# IDD_measurement.net
KiCad netlist of a schematic drawn in Altium Designer
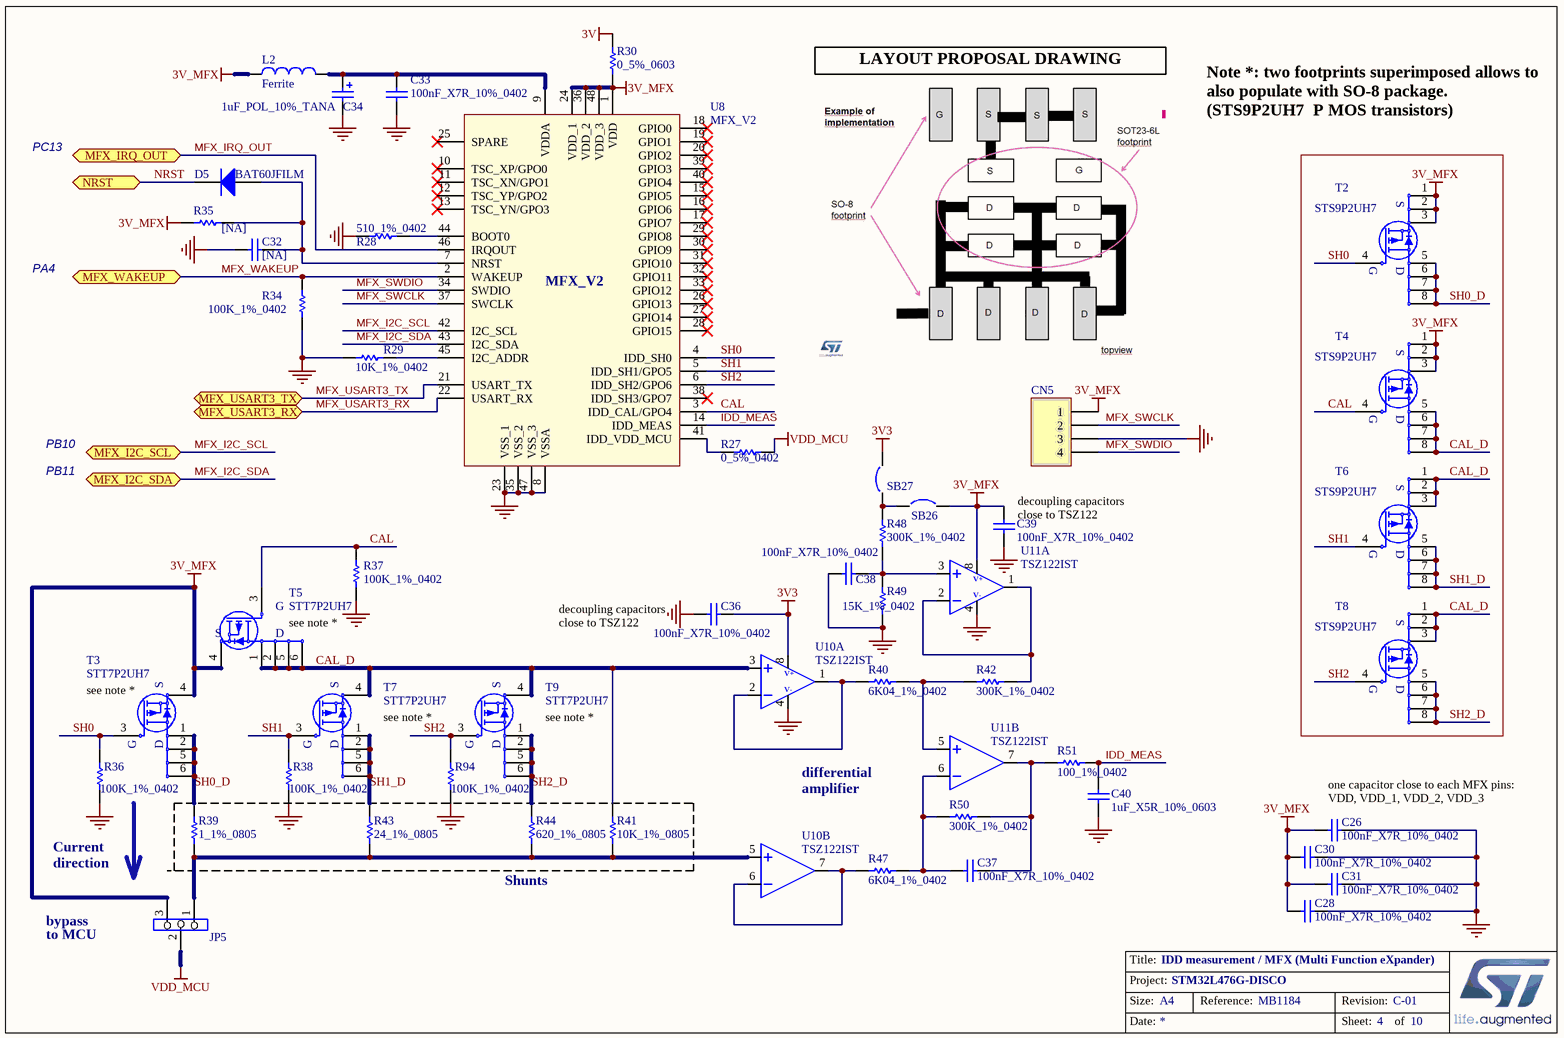
[diagram p0: IDD_measurement.SchDoc]

(export (version "E")
  (design (tool "Eeschema 10.0.6"))
  (components
    (comp (ref "C26")
      (value "100nF_X7R_10%_0402")
      (footprint "0402C")
      (description "Capacitor,100nF,16V,X7R,10%,0402,YAGEO")
      (libsource (lib "MCD_TOOLS") (part "Cap_100nF_X7R_10%_0402"))
    )
    (comp (ref "C28")
      (value "100nF_X7R_10%_0402")
      (footprint "0402C")
      (description "Capacitor,100nF,16V,X7R,10%,0402,YAGEO")
      (libsource (lib "MCD_TOOLS") (part "Cap_100nF_X7R_10%_0402"))
    )
    (comp (ref "C30")
      (value "100nF_X7R_10%_0402")
      (footprint "0402C")
      (description "Capacitor,100nF,16V,X7R,10%,0402,YAGEO")
      (libsource (lib "MCD_TOOLS") (part "Cap_100nF_X7R_10%_0402"))
    )
    (comp (ref "C31")
      (value "100nF_X7R_10%_0402")
      (footprint "0402C")
      (description "Capacitor,100nF,16V,X7R,10%,0402,YAGEO")
      (libsource (lib "MCD_TOOLS") (part "Cap_100nF_X7R_10%_0402"))
    )
    (comp (ref "C32")
      (value "[NA]")
      (footprint "0402C")
      (description "Capacitor,NA,0402")
      (libsource (lib "MCD_TOOLS") (part "Cap_NA_0402"))
    )
    (comp (ref "C33")
      (value "100nF_X7R_10%_0402")
      (footprint "0402C")
      (description "Capacitor,100nF,16V,X7R,10%,0402,YAGEO")
      (libsource (lib "MCD_TOOLS") (part "Cap_100nF_X7R_10%_0402"))
    )
    (comp (ref "C34")
      (value "1uF_POL_10%_TANA")
      (footprint "TAN-A")
      (description "Polarized Capacitor,1uF,16V,10%,typeA,AVX")
      (libsource (lib "MCD_TOOLS") (part "Cap_1uF_POL_10%_TANA"))
    )
    (comp (ref "C36")
      (value "100nF_X7R_10%_0402")
      (footprint "0402C")
      (description "Capacitor,100nF,16V,X7R,10%,0402,YAGEO")
      (libsource (lib "MCD_TOOLS") (part "Cap_100nF_X7R_10%_0402"))
    )
    (comp (ref "C37")
      (value "100nF_X7R_10%_0402")
      (footprint "0402C")
      (description "Capacitor,100nF,16V,X7R,10%,0402,YAGEO")
      (libsource (lib "MCD_TOOLS") (part "Cap_100nF_X7R_10%_0402"))
    )
    (comp (ref "C38")
      (value "100nF_X7R_10%_0402")
      (footprint "0402C")
      (description "Capacitor,100nF,16V,X7R,10%,0402,YAGEO")
      (libsource (lib "MCD_TOOLS") (part "Cap_100nF_X7R_10%_0402"))
    )
    (comp (ref "C39")
      (value "100nF_X7R_10%_0402")
      (footprint "0402C")
      (description "Capacitor,100nF,16V,X7R,10%,0402,YAGEO")
      (libsource (lib "MCD_TOOLS") (part "Cap_100nF_X7R_10%_0402"))
    )
    (comp (ref "C40")
      (value "1uF_X5R_10%_0603")
      (footprint "0603C")
      (description "Capacitor,1uF,16V,X5R,10%,0603,YAGEO")
      (libsource (lib "MCD_TOOLS") (part "Cap_1uF_X5R_10%_0603"))
    )
    (comp (ref "CN5")
      (value "Header 4")
      (footprint "Header 4")
      (description "Header, 4-Pin")
      (fields (field (name "PUBLISHER") "Altium Limited"))
      (libsource (lib "MCD_TOOLS") (part "Header 4"))
    )
    (comp (ref "D5")
      (value "BAT60JFILM")
      (footprint "SOD323/A")
      (libsource (lib "MCD_TOOLS") (part "BAT60JFILM"))
    )
    (comp (ref "JP5")
      (value "Jumper 3 pins")
      (footprint "SIP3")
      (libsource (lib "MCD_TOOLS") (part "Jumper3"))
    )
    (comp (ref "L2")
      (value "Ferrite")
      (footprint "0603L")
      (description "Bead,600R,350mA,0603,FCM1608KF-601T03,Tai-tech")
      (libsource (lib "MCD_TOOLS") (part "BEAD_600R_350MA_0603"))
    )
    (comp (ref "R27")
      (value "0_5%_0402")
      (footprint "0402R")
      (description "Resistor,0,0402,5%,YAGEO")
      (libsource (lib "MCD_TOOLS") (part "Res_0_5%_0402"))
    )
    (comp (ref "R28")
      (value "510_1%_0402")
      (footprint "0402R")
      (description "Resistor,510,0402,1%,YAGEO")
      (libsource (lib "MCD_TOOLS") (part "Res_510_1%_0402"))
    )
    (comp (ref "R29")
      (value "10K_1%_0402")
      (footprint "0402R")
      (description "Resistor,10K,0402,1%,YAGEO")
      (libsource (lib "MCD_TOOLS") (part "Res_10K_1%_0402"))
    )
    (comp (ref "R30")
      (value "0_5%_0603")
      (footprint "0603R-GS")
      (description "Resistor,0,0603,5%,YAGEO")
      (libsource (lib "MCD_TOOLS") (part "Res_0_5%_0603"))
    )
    (comp (ref "R34")
      (value "100K_1%_0402")
      (footprint "0402R")
      (description "Resistor,100K,0402,1%,YAGEO")
      (libsource (lib "MCD_TOOLS") (part "Res_100K_1%_0402"))
    )
    (comp (ref "R35")
      (value "[NA]")
      (footprint "0402R")
      (description "Resistor,[NA],0402")
      (libsource (lib "MCD_TOOLS") (part "Res_NA_0402"))
    )
    (comp (ref "R36")
      (value "100K_1%_0402")
      (footprint "0402R")
      (description "Resistor,100K,0402,1%,YAGEO")
      (libsource (lib "MCD_TOOLS") (part "Res_100K_1%_0402"))
    )
    (comp (ref "R37")
      (value "100K_1%_0402")
      (footprint "0402R")
      (description "Resistor,100K,0402,1%,YAGEO")
      (libsource (lib "MCD_TOOLS") (part "Res_100K_1%_0402"))
    )
    (comp (ref "R38")
      (value "100K_1%_0402")
      (footprint "0402R")
      (description "Resistor,100K,0402,1%,YAGEO")
      (libsource (lib "MCD_TOOLS") (part "Res_100K_1%_0402"))
    )
    (comp (ref "R39")
      (value "1_1%_0805")
      (footprint "0805R")
      (description "Resistor,1,0805,1%,YAGEO")
      (libsource (lib "MCD_TOOLS") (part "Res_1_1%_0805"))
    )
    (comp (ref "R40")
      (value "6K04_1%_0402")
      (footprint "0402R")
      (description "Resistor,6K04,0402,1%,YAGEO")
      (libsource (lib "MCD_TOOLS") (part "Res_6K04_1%_0402"))
    )
    (comp (ref "R41")
      (value "10K_1%_0805")
      (footprint "0805R")
      (description "Resistor,10K,0805,1%,YAGEO")
      (libsource (lib "MCD_TOOLS") (part "Res_10K_1%_0805"))
    )
    (comp (ref "R42")
      (value "300K_1%_0402")
      (footprint "0402R")
      (description "Resistor,300K,0402,1%,YAGEO")
      (libsource (lib "MCD_TOOLS") (part "Res_300K_1%_0402"))
    )
    (comp (ref "R43")
      (value "24_1%_0805")
      (footprint "0805R")
      (description "Resistor,24,0805,1%,YAGEO")
      (libsource (lib "MCD_TOOLS") (part "Res_24_1%_0805"))
    )
    (comp (ref "R44")
      (value "620_1%_0805")
      (footprint "0805R")
      (description "Resistor,620,0805,1%,YAGEO")
      (libsource (lib "MCD_TOOLS") (part "Res_620_1%_0805"))
    )
    (comp (ref "R47")
      (value "6K04_1%_0402")
      (footprint "0402R")
      (description "Resistor,6K04,0402,1%,YAGEO")
      (libsource (lib "MCD_TOOLS") (part "Res_6K04_1%_0402"))
    )
    (comp (ref "R48")
      (value "300K_1%_0402")
      (footprint "0402R")
      (description "Resistor,300K,0402,1%,YAGEO")
      (libsource (lib "MCD_TOOLS") (part "Res_300K_1%_0402"))
    )
    (comp (ref "R49")
      (value "15K_1%_0402")
      (footprint "0402R")
      (description "Resistor,15K,0402,1%,YAGEO")
      (libsource (lib "MCD_TOOLS") (part "Res_15K_1%_0402"))
    )
    (comp (ref "R50")
      (value "300K_1%_0402")
      (footprint "0402R")
      (description "Resistor,300K,0402,1%,YAGEO")
      (libsource (lib "MCD_TOOLS") (part "Res_300K_1%_0402"))
    )
    (comp (ref "R51")
      (value "100_1%_0402")
      (footprint "0402R")
      (description "Resistor,100,0402,1%,YAGEO")
      (libsource (lib "MCD_TOOLS") (part "Res_100_1%_0402"))
    )
    (comp (ref "R94")
      (value "100K_1%_0402")
      (footprint "0402R")
      (description "Resistor,100K,0402,1%,YAGEO")
      (libsource (lib "MCD_TOOLS") (part "Res_100K_1%_0402"))
    )
    (comp (ref "SB26")
      (value "Circuit Breaker")
      (footprint "JP2_SMD")
      (libsource (lib "MCD_TOOLS") (part "Circuit Breaker"))
    )
    (comp (ref "SB27")
      (value "Circuit Breaker")
      (footprint "JP2_SMD")
      (libsource (lib "MCD_TOOLS") (part "Circuit Breaker"))
    )
    (comp (ref "T2")
      (value "STS9P2UH7")
      (footprint "SO8")
      (description "STripFET VII Power MOSFET, P-CHANNEL 20V - 0.023 - 7A - SO-8")
      (libsource (lib "MCD_TOOLS") (part "STS7P2UH7"))
    )
    (comp (ref "T3")
      (value "STT7P2UH7")
      (footprint "SOT23-6L")
      (description "STripFET VII DeepGATE Power MOSFET, P-CHANNEL 20 V, 0.0146, 7 A - SOT23-6L")
      (libsource (lib "MCD_TOOLS") (part "STT7P2UH7"))
    )
    (comp (ref "T4")
      (value "STS9P2UH7")
      (footprint "SO8")
      (description "STripFET VII Power MOSFET, P-CHANNEL 20V - 0.023 - 7A - SO-8")
      (libsource (lib "MCD_TOOLS") (part "STS7P2UH7"))
    )
    (comp (ref "T5")
      (value "STT7P2UH7")
      (footprint "SOT23-6L")
      (description "STripFET VII DeepGATE Power MOSFET, P-CHANNEL 20 V, 0.0146, 7 A - SOT23-6L")
      (libsource (lib "MCD_TOOLS") (part "STT7P2UH7"))
    )
    (comp (ref "T6")
      (value "STS9P2UH7")
      (footprint "SO8")
      (description "STripFET VII Power MOSFET, P-CHANNEL 20V - 0.023 - 7A - SO-8")
      (libsource (lib "MCD_TOOLS") (part "STS7P2UH7"))
    )
    (comp (ref "T7")
      (value "STT7P2UH7")
      (footprint "SOT23-6L")
      (description "STripFET VII DeepGATE Power MOSFET, P-CHANNEL 20 V, 0.0146, 7 A - SOT23-6L")
      (libsource (lib "MCD_TOOLS") (part "STT7P2UH7"))
    )
    (comp (ref "T8")
      (value "STS9P2UH7")
      (footprint "SO8")
      (description "STripFET VII Power MOSFET, P-CHANNEL 20V - 0.023 - 7A - SO-8")
      (libsource (lib "MCD_TOOLS") (part "STS7P2UH7"))
    )
    (comp (ref "T9")
      (value "STT7P2UH7")
      (footprint "SOT23-6L")
      (description "STripFET VII DeepGATE Power MOSFET, P-CHANNEL 20 V, 0.0146, 7 A - SOT23-6L")
      (libsource (lib "MCD_TOOLS") (part "STT7P2UH7"))
    )
    (comp (ref "U8")
      (value "MFX_V2")
      (footprint "QFP48 7X7")
      (description "MultiFunction eXpander (STM32L152CCT6)")
      (libsource (lib "MCD_TOOLS") (part "MFX_V2"))
    )
    (comp (ref "U10")
      (value "TSZ122IST")
      (footprint "miniSO8")
      (description "Very high accuracy (5 µV) zero drift 5 V dual OpAmp")
      (libsource (lib "MCD_TOOLS") (part "TSZ122IST"))
    )
    (comp (ref "U11")
      (value "TSZ122IST")
      (footprint "miniSO8")
      (description "Very high accuracy (5 µV) zero drift 5 V dual OpAmp")
      (libsource (lib "MCD_TOOLS") (part "TSZ122IST"))
    )
  )
  (nets
    (net (code "1") (name "/CAL") (class "Default")
      (node (ref "R37") (pin "2") (pinfunction "2_2") (pintype "passive"))
      (node (ref "T4") (pin "4") (pinfunction "G_4") (pintype "passive"))
      (node (ref "T5") (pin "3") (pinfunction "G_3") (pintype "passive"))
      (node (ref "U8") (pin "3") (pinfunction "IDD_CAL/GPO4_3") (pintype "passive"))
    )
    (net (code "2") (name "/CAL_D") (class "Default")
      (node (ref "R41") (pin "2") (pinfunction "2_2") (pintype "passive"))
      (node (ref "T4") (pin "5") (pinfunction "D_5") (pintype "passive"))
      (node (ref "T4") (pin "6") (pinfunction "D_6") (pintype "passive"))
      (node (ref "T4") (pin "7") (pinfunction "D_7") (pintype "passive"))
      (node (ref "T4") (pin "8") (pinfunction "D_8") (pintype "passive"))
      (node (ref "T5") (pin "1") (pinfunction "S_1") (pintype "passive"))
      (node (ref "T5") (pin "2") (pinfunction "S_2") (pintype "passive"))
      (node (ref "T5") (pin "5") (pinfunction "D_5") (pintype "passive"))
      (node (ref "T5") (pin "6") (pinfunction "D_6") (pintype "passive"))
      (node (ref "T6") (pin "1") (pinfunction "S_1") (pintype "passive"))
      (node (ref "T6") (pin "2") (pinfunction "S_2") (pintype "passive"))
      (node (ref "T6") (pin "3") (pinfunction "S_3") (pintype "passive"))
      (node (ref "T7") (pin "4") (pinfunction "S_4") (pintype "passive"))
      (node (ref "T8") (pin "1") (pinfunction "S_1") (pintype "passive"))
      (node (ref "T8") (pin "2") (pinfunction "S_2") (pintype "passive"))
      (node (ref "T8") (pin "3") (pinfunction "S_3") (pintype "passive"))
      (node (ref "T9") (pin "4") (pinfunction "S_4") (pintype "passive"))
      (node (ref "U10") (pin "3") (pintype "passive"))
    )
    (net (code "3") (name "/IDD_MEAS") (class "Default")
      (node (ref "C40") (pin "2") (pinfunction "2_2") (pintype "passive"))
      (node (ref "R51") (pin "2") (pinfunction "2_2") (pintype "passive"))
      (node (ref "U8") (pin "14") (pinfunction "IDD_MEAS_14") (pintype "passive"))
    )
    (net (code "4") (name "/MFX_I2C_SCL") (class "Default")
      (node (ref "U8") (pin "42") (pinfunction "I2C_SCL_42") (pintype "passive"))
    )
    (net (code "5") (name "/MFX_I2C_SDA") (class "Default")
      (node (ref "U8") (pin "43") (pinfunction "I2C_SDA_43") (pintype "passive"))
    )
    (net (code "6") (name "/MFX_IRQ_OUT") (class "Default")
      (node (ref "U8") (pin "46") (pinfunction "IRQOUT_46") (pintype "passive"))
    )
    (net (code "7") (name "/MFX_SWCLK") (class "Default")
      (node (ref "CN5") (pin "2") (pinfunction "2_2") (pintype "passive"))
      (node (ref "U8") (pin "37") (pinfunction "SWCLK_37") (pintype "passive"))
    )
    (net (code "8") (name "/MFX_SWDIO") (class "Default")
      (node (ref "CN5") (pin "4") (pinfunction "4_4") (pintype "passive"))
      (node (ref "U8") (pin "34") (pinfunction "SWDIO_34") (pintype "passive"))
    )
    (net (code "9") (name "/MFX_USART3_RX") (class "Default")
      (node (ref "U8") (pin "22") (pinfunction "USART_RX_22") (pintype "passive"))
    )
    (net (code "10") (name "/MFX_USART3_TX") (class "Default")
      (node (ref "U8") (pin "21") (pinfunction "USART_TX_21") (pintype "passive"))
    )
    (net (code "11") (name "/MFX_WAKEUP") (class "Default")
      (node (ref "R34") (pin "2") (pinfunction "2_2") (pintype "passive"))
      (node (ref "U8") (pin "2") (pinfunction "WAKEUP_2") (pintype "passive"))
    )
    (net (code "12") (name "/NRST") (class "Default")
      (node (ref "D5") (pin "2") (pinfunction "K_2") (pintype "passive"))
    )
    (net (code "13") (name "/SH0") (class "Default")
      (node (ref "R36") (pin "2") (pinfunction "2_2") (pintype "passive"))
      (node (ref "T2") (pin "4") (pinfunction "G_4") (pintype "passive"))
      (node (ref "T3") (pin "3") (pinfunction "G_3") (pintype "passive"))
      (node (ref "U8") (pin "4") (pinfunction "IDD_SH0_4") (pintype "passive"))
    )
    (net (code "14") (name "/SH0_D") (class "Default")
      (node (ref "R39") (pin "2") (pinfunction "2_2") (pintype "passive"))
      (node (ref "T2") (pin "5") (pinfunction "D_5") (pintype "passive"))
      (node (ref "T2") (pin "6") (pinfunction "D_6") (pintype "passive"))
      (node (ref "T2") (pin "7") (pinfunction "D_7") (pintype "passive"))
      (node (ref "T2") (pin "8") (pinfunction "D_8") (pintype "passive"))
      (node (ref "T3") (pin "1") (pinfunction "S_1") (pintype "passive"))
      (node (ref "T3") (pin "2") (pinfunction "S_2") (pintype "passive"))
      (node (ref "T3") (pin "5") (pinfunction "D_5") (pintype "passive"))
      (node (ref "T3") (pin "6") (pinfunction "D_6") (pintype "passive"))
    )
    (net (code "15") (name "/SH1") (class "Default")
      (node (ref "R38") (pin "2") (pinfunction "2_2") (pintype "passive"))
      (node (ref "T6") (pin "4") (pinfunction "G_4") (pintype "passive"))
      (node (ref "T7") (pin "3") (pinfunction "G_3") (pintype "passive"))
      (node (ref "U8") (pin "5") (pinfunction "IDD_SH1/GPO5_5") (pintype "passive"))
    )
    (net (code "16") (name "/SH1_D") (class "Default")
      (node (ref "R43") (pin "2") (pinfunction "2_2") (pintype "passive"))
      (node (ref "T6") (pin "5") (pinfunction "D_5") (pintype "passive"))
      (node (ref "T6") (pin "6") (pinfunction "D_6") (pintype "passive"))
      (node (ref "T6") (pin "7") (pinfunction "D_7") (pintype "passive"))
      (node (ref "T6") (pin "8") (pinfunction "D_8") (pintype "passive"))
      (node (ref "T7") (pin "1") (pinfunction "S_1") (pintype "passive"))
      (node (ref "T7") (pin "2") (pinfunction "S_2") (pintype "passive"))
      (node (ref "T7") (pin "5") (pinfunction "D_5") (pintype "passive"))
      (node (ref "T7") (pin "6") (pinfunction "D_6") (pintype "passive"))
    )
    (net (code "17") (name "/SH2") (class "Default")
      (node (ref "R94") (pin "2") (pinfunction "2_2") (pintype "passive"))
      (node (ref "T8") (pin "4") (pinfunction "G_4") (pintype "passive"))
      (node (ref "T9") (pin "3") (pinfunction "G_3") (pintype "passive"))
      (node (ref "U8") (pin "6") (pinfunction "IDD_SH2/GPO6_6") (pintype "passive"))
    )
    (net (code "18") (name "/SH2_D") (class "Default")
      (node (ref "R44") (pin "2") (pinfunction "2_2") (pintype "passive"))
      (node (ref "T8") (pin "5") (pinfunction "D_5") (pintype "passive"))
      (node (ref "T8") (pin "6") (pinfunction "D_6") (pintype "passive"))
      (node (ref "T8") (pin "7") (pinfunction "D_7") (pintype "passive"))
      (node (ref "T8") (pin "8") (pinfunction "D_8") (pintype "passive"))
      (node (ref "T9") (pin "1") (pinfunction "S_1") (pintype "passive"))
      (node (ref "T9") (pin "2") (pinfunction "S_2") (pintype "passive"))
      (node (ref "T9") (pin "5") (pinfunction "D_5") (pintype "passive"))
      (node (ref "T9") (pin "6") (pinfunction "D_6") (pintype "passive"))
    )
    (net (code "19") (name "3V") (class "Default")
      (node (ref "R30") (pin "2") (pinfunction "2_2") (pintype "passive"))
    )
    (net (code "20") (name "3V3") (class "Default")
      (node (ref "C36") (pin "2") (pinfunction "2_2") (pintype "passive"))
      (node (ref "SB27") (pin "2") (pinfunction "2_2") (pintype "passive"))
      (node (ref "U10") (pin "8") (pintype "passive"))
    )
    (net (code "21") (name "3V_MFX") (class "Default")
      (node (ref "C26") (pin "1") (pinfunction "1_1") (pintype "passive"))
      (node (ref "C28") (pin "1") (pinfunction "1_1") (pintype "passive"))
      (node (ref "C30") (pin "1") (pinfunction "1_1") (pintype "passive"))
      (node (ref "C31") (pin "1") (pinfunction "1_1") (pintype "passive"))
      (node (ref "C39") (pin "2") (pinfunction "2_2") (pintype "passive"))
      (node (ref "CN5") (pin "1") (pinfunction "1_1") (pintype "passive"))
      (node (ref "JP5") (pin "3") (pintype "passive"))
      (node (ref "L2") (pin "1") (pinfunction "1_1") (pintype "passive"))
      (node (ref "R30") (pin "1") (pinfunction "1_1") (pintype "passive"))
      (node (ref "R35") (pin "1") (pinfunction "1_1") (pintype "passive"))
      (node (ref "SB26") (pin "2") (pinfunction "2_2") (pintype "passive"))
      (node (ref "T2") (pin "1") (pinfunction "S_1") (pintype "passive"))
      (node (ref "T2") (pin "2") (pinfunction "S_2") (pintype "passive"))
      (node (ref "T2") (pin "3") (pinfunction "S_3") (pintype "passive"))
      (node (ref "T3") (pin "4") (pinfunction "S_4") (pintype "passive"))
      (node (ref "T4") (pin "1") (pinfunction "S_1") (pintype "passive"))
      (node (ref "T4") (pin "2") (pinfunction "S_2") (pintype "passive"))
      (node (ref "T4") (pin "3") (pinfunction "S_3") (pintype "passive"))
      (node (ref "T5") (pin "4") (pinfunction "S_4") (pintype "passive"))
      (node (ref "U11") (pin "8") (pintype "passive"))
      (node (ref "U8") (pin "1") (pinfunction "VDD_1") (pintype "passive"))
      (node (ref "U8") (pin "24") (pinfunction "VDD_1_24") (pintype "passive"))
      (node (ref "U8") (pin "36") (pinfunction "VDD_2_36") (pintype "passive"))
      (node (ref "U8") (pin "48") (pinfunction "VDD_3_48") (pintype "passive"))
    )
    (net (code "22") (name "GND") (class "Default")
      (node (ref "C26") (pin "2") (pinfunction "2_2") (pintype "passive"))
      (node (ref "C28") (pin "2") (pinfunction "2_2") (pintype "passive"))
      (node (ref "C30") (pin "2") (pinfunction "2_2") (pintype "passive"))
      (node (ref "C31") (pin "2") (pinfunction "2_2") (pintype "passive"))
      (node (ref "C32") (pin "1") (pinfunction "1_1") (pintype "passive"))
      (node (ref "C33") (pin "1") (pinfunction "1_1") (pintype "passive"))
      (node (ref "C34") (pin "2") (pinfunction "2_2") (pintype "passive"))
      (node (ref "C36") (pin "1") (pinfunction "1_1") (pintype "passive"))
      (node (ref "C38") (pin "1") (pinfunction "1_1") (pintype "passive"))
      (node (ref "C39") (pin "1") (pinfunction "1_1") (pintype "passive"))
      (node (ref "C40") (pin "1") (pinfunction "1_1") (pintype "passive"))
      (node (ref "CN5") (pin "3") (pinfunction "3_3") (pintype "passive"))
      (node (ref "R28") (pin "1") (pinfunction "1_1") (pintype "passive"))
      (node (ref "R29") (pin "1") (pinfunction "1_1") (pintype "passive"))
      (node (ref "R34") (pin "1") (pinfunction "1_1") (pintype "passive"))
      (node (ref "R36") (pin "1") (pinfunction "1_1") (pintype "passive"))
      (node (ref "R37") (pin "1") (pinfunction "1_1") (pintype "passive"))
      (node (ref "R38") (pin "1") (pinfunction "1_1") (pintype "passive"))
      (node (ref "R49") (pin "1") (pinfunction "1_1") (pintype "passive"))
      (node (ref "R94") (pin "1") (pinfunction "1_1") (pintype "passive"))
      (node (ref "U10") (pin "4") (pintype "passive"))
      (node (ref "U11") (pin "4") (pintype "passive"))
      (node (ref "U8") (pin "23") (pinfunction "VSS_1_23") (pintype "passive"))
      (node (ref "U8") (pin "35") (pinfunction "VSS_2_35") (pintype "passive"))
      (node (ref "U8") (pin "47") (pinfunction "VSS_3_47") (pintype "passive"))
      (node (ref "U8") (pin "8") (pinfunction "VSSA_8") (pintype "passive"))
    )
    (net (code "23") (name "Net-(C37-Pad1)") (class "Default")
      (node (ref "C37") (pin "1") (pinfunction "1_1") (pintype "passive"))
      (node (ref "R47") (pin "2") (pinfunction "2_2") (pintype "passive"))
      (node (ref "R50") (pin "1") (pinfunction "1_1") (pintype "passive"))
      (node (ref "U11") (pin "6") (pintype "passive"))
    )
    (net (code "24") (name "Net-(C37-Pad2)") (class "Default")
      (node (ref "C37") (pin "2") (pinfunction "2_2") (pintype "passive"))
      (node (ref "R50") (pin "2") (pinfunction "2_2") (pintype "passive"))
      (node (ref "R51") (pin "1") (pinfunction "1_1") (pintype "passive"))
      (node (ref "U11") (pin "7") (pintype "passive"))
    )
    (net (code "25") (name "Net-(C38-Pad2)") (class "Default")
      (node (ref "C38") (pin "2") (pinfunction "2_2") (pintype "passive"))
      (node (ref "R48") (pin "1") (pinfunction "1_1") (pintype "passive"))
      (node (ref "R49") (pin "2") (pinfunction "2_2") (pintype "passive"))
      (node (ref "U11") (pin "3") (pintype "passive"))
    )
    (net (code "26") (name "Net-(D5-A)") (class "Default")
      (node (ref "C32") (pin "2") (pinfunction "2_2") (pintype "passive"))
      (node (ref "D5") (pin "1") (pinfunction "A_1") (pintype "passive"))
      (node (ref "R35") (pin "2") (pinfunction "2_2") (pintype "passive"))
      (node (ref "U8") (pin "7") (pinfunction "NRST_7") (pintype "passive"))
    )
    (net (code "27") (name "Net-(JP5-Pad1)") (class "Default")
      (node (ref "JP5") (pin "1") (pintype "passive"))
      (node (ref "R39") (pin "1") (pinfunction "1_1") (pintype "passive"))
      (node (ref "R41") (pin "1") (pinfunction "1_1") (pintype "passive"))
      (node (ref "R43") (pin "1") (pinfunction "1_1") (pintype "passive"))
      (node (ref "R44") (pin "1") (pinfunction "1_1") (pintype "passive"))
      (node (ref "U10") (pin "5") (pintype "passive"))
    )
    (net (code "28") (name "Net-(R40-Pad1)") (class "Default")
      (node (ref "R40") (pin "1") (pinfunction "1_1") (pintype "passive"))
      (node (ref "U10") (pin "1") (pintype "passive"))
      (node (ref "U10") (pin "2") (pintype "passive"))
    )
    (net (code "29") (name "Net-(R40-Pad2)") (class "Default")
      (node (ref "R40") (pin "2") (pinfunction "2_2") (pintype "passive"))
      (node (ref "R42") (pin "1") (pinfunction "1_1") (pintype "passive"))
      (node (ref "U11") (pin "5") (pintype "passive"))
    )
    (net (code "30") (name "Net-(R42-Pad2)") (class "Default")
      (node (ref "R42") (pin "2") (pinfunction "2_2") (pintype "passive"))
      (node (ref "U11") (pin "1") (pintype "passive"))
      (node (ref "U11") (pin "2") (pintype "passive"))
    )
    (net (code "31") (name "Net-(R47-Pad1)") (class "Default")
      (node (ref "R47") (pin "1") (pinfunction "1_1") (pintype "passive"))
      (node (ref "U10") (pin "6") (pintype "passive"))
      (node (ref "U10") (pin "7") (pintype "passive"))
    )
    (net (code "32") (name "Net-(R48-Pad2)") (class "Default")
      (node (ref "R48") (pin "2") (pinfunction "2_2") (pintype "passive"))
      (node (ref "SB26") (pin "1") (pinfunction "1_1") (pintype "passive"))
      (node (ref "SB27") (pin "1") (pinfunction "1_1") (pintype "passive"))
    )
    (net (code "33") (name "Net-(U8-BOOT0)") (class "Default")
      (node (ref "R28") (pin "2") (pinfunction "2_2") (pintype "passive"))
      (node (ref "U8") (pin "44") (pinfunction "BOOT0_44") (pintype "passive"))
    )
    (net (code "34") (name "Net-(U8-I2C_ADDR)") (class "Default")
      (node (ref "R29") (pin "2") (pinfunction "2_2") (pintype "passive"))
      (node (ref "U8") (pin "45") (pinfunction "I2C_ADDR_45") (pintype "passive"))
    )
    (net (code "35") (name "Net-(U8-IDD_VDD_MCU)") (class "Default")
      (node (ref "R27") (pin "1") (pinfunction "1_1") (pintype "passive"))
      (node (ref "U8") (pin "41") (pinfunction "IDD_VDD_MCU_41") (pintype "passive"))
    )
    (net (code "36") (name "Net-(U8-VDDA)") (class "Default")
      (node (ref "C33") (pin "2") (pinfunction "2_2") (pintype "passive"))
      (node (ref "C34") (pin "1") (pinfunction "1_1") (pintype "passive"))
      (node (ref "L2") (pin "2") (pinfunction "2_2") (pintype "passive"))
      (node (ref "U8") (pin "9") (pinfunction "VDDA_9") (pintype "passive"))
    )
    (net (code "37") (name "VDD_MCU") (class "Default")
      (node (ref "JP5") (pin "2") (pintype "passive"))
      (node (ref "R27") (pin "2") (pinfunction "2_2") (pintype "passive"))
    )
    (net (code "38") (name "unconnected-(U8-GPIO0-Pad18)") (class "Default")
      (node (ref "U8") (pin "18") (pinfunction "GPIO0_18") (pintype "passive+no_connect"))
    )
    (net (code "39") (name "unconnected-(U8-GPIO1-Pad19)") (class "Default")
      (node (ref "U8") (pin "19") (pinfunction "GPIO1_19") (pintype "passive+no_connect"))
    )
    (net (code "40") (name "unconnected-(U8-GPIO2-Pad20)") (class "Default")
      (node (ref "U8") (pin "20") (pinfunction "GPIO2_20") (pintype "passive+no_connect"))
    )
    (net (code "41") (name "unconnected-(U8-GPIO3-Pad39)") (class "Default")
      (node (ref "U8") (pin "39") (pinfunction "GPIO3_39") (pintype "passive+no_connect"))
    )
    (net (code "42") (name "unconnected-(U8-GPIO4-Pad40)") (class "Default")
      (node (ref "U8") (pin "40") (pinfunction "GPIO4_40") (pintype "passive+no_connect"))
    )
    (net (code "43") (name "unconnected-(U8-GPIO5-Pad15)") (class "Default")
      (node (ref "U8") (pin "15") (pinfunction "GPIO5_15") (pintype "passive+no_connect"))
    )
    (net (code "44") (name "unconnected-(U8-GPIO6-Pad16)") (class "Default")
      (node (ref "U8") (pin "16") (pinfunction "GPIO6_16") (pintype "passive+no_connect"))
    )
    (net (code "45") (name "unconnected-(U8-GPIO7-Pad17)") (class "Default")
      (node (ref "U8") (pin "17") (pinfunction "GPIO7_17") (pintype "passive+no_connect"))
    )
    (net (code "46") (name "unconnected-(U8-GPIO8-Pad29)") (class "Default")
      (node (ref "U8") (pin "29") (pinfunction "GPIO8_29") (pintype "passive+no_connect"))
    )
    (net (code "47") (name "unconnected-(U8-GPIO9-Pad30)") (class "Default")
      (node (ref "U8") (pin "30") (pinfunction "GPIO9_30") (pintype "passive+no_connect"))
    )
    (net (code "48") (name "unconnected-(U8-GPIO10-Pad31)") (class "Default")
      (node (ref "U8") (pin "31") (pinfunction "GPIO10_31") (pintype "passive+no_connect"))
    )
    (net (code "49") (name "unconnected-(U8-GPIO11-Pad32)") (class "Default")
      (node (ref "U8") (pin "32") (pinfunction "GPIO11_32") (pintype "passive+no_connect"))
    )
    (net (code "50") (name "unconnected-(U8-GPIO12-Pad33)") (class "Default")
      (node (ref "U8") (pin "33") (pinfunction "GPIO12_33") (pintype "passive+no_connect"))
    )
    (net (code "51") (name "unconnected-(U8-GPIO13-Pad26)") (class "Default")
      (node (ref "U8") (pin "26") (pinfunction "GPIO13_26") (pintype "passive+no_connect"))
    )
    (net (code "52") (name "unconnected-(U8-GPIO14-Pad27)") (class "Default")
      (node (ref "U8") (pin "27") (pinfunction "GPIO14_27") (pintype "passive+no_connect"))
    )
    (net (code "53") (name "unconnected-(U8-GPIO15-Pad28)") (class "Default")
      (node (ref "U8") (pin "28") (pinfunction "GPIO15_28") (pintype "passive+no_connect"))
    )
    (net (code "54") (name "unconnected-(U8-IDD_SH3{slash}GPO7-Pad38)") (class "Default")
      (node (ref "U8") (pin "38") (pinfunction "IDD_SH3/GPO7_38") (pintype "passive+no_connect"))
    )
    (net (code "55") (name "unconnected-(U8-SPARE-Pad25)") (class "Default")
      (node (ref "U8") (pin "25") (pinfunction "SPARE_25") (pintype "passive+no_connect"))
    )
    (net (code "56") (name "unconnected-(U8-TSC_XN{slash}GPO1-Pad11)") (class "Default")
      (node (ref "U8") (pin "11") (pinfunction "TSC_XN/GPO1_11") (pintype "passive+no_connect"))
    )
    (net (code "57") (name "unconnected-(U8-TSC_XP{slash}GPO0-Pad10)") (class "Default")
      (node (ref "U8") (pin "10") (pinfunction "TSC_XP/GPO0_10") (pintype "passive+no_connect"))
    )
    (net (code "58") (name "unconnected-(U8-TSC_YN{slash}GPO3-Pad13)") (class "Default")
      (node (ref "U8") (pin "13") (pinfunction "TSC_YN/GPO3_13") (pintype "passive+no_connect"))
    )
    (net (code "59") (name "unconnected-(U8-TSC_YP{slash}GPO2-Pad12)") (class "Default")
      (node (ref "U8") (pin "12") (pinfunction "TSC_YP/GPO2_12") (pintype "passive+no_connect"))
    )
  )
)
